# CV_converter_v06.net
KiCad netlist of a schematic drawn in EAGLE
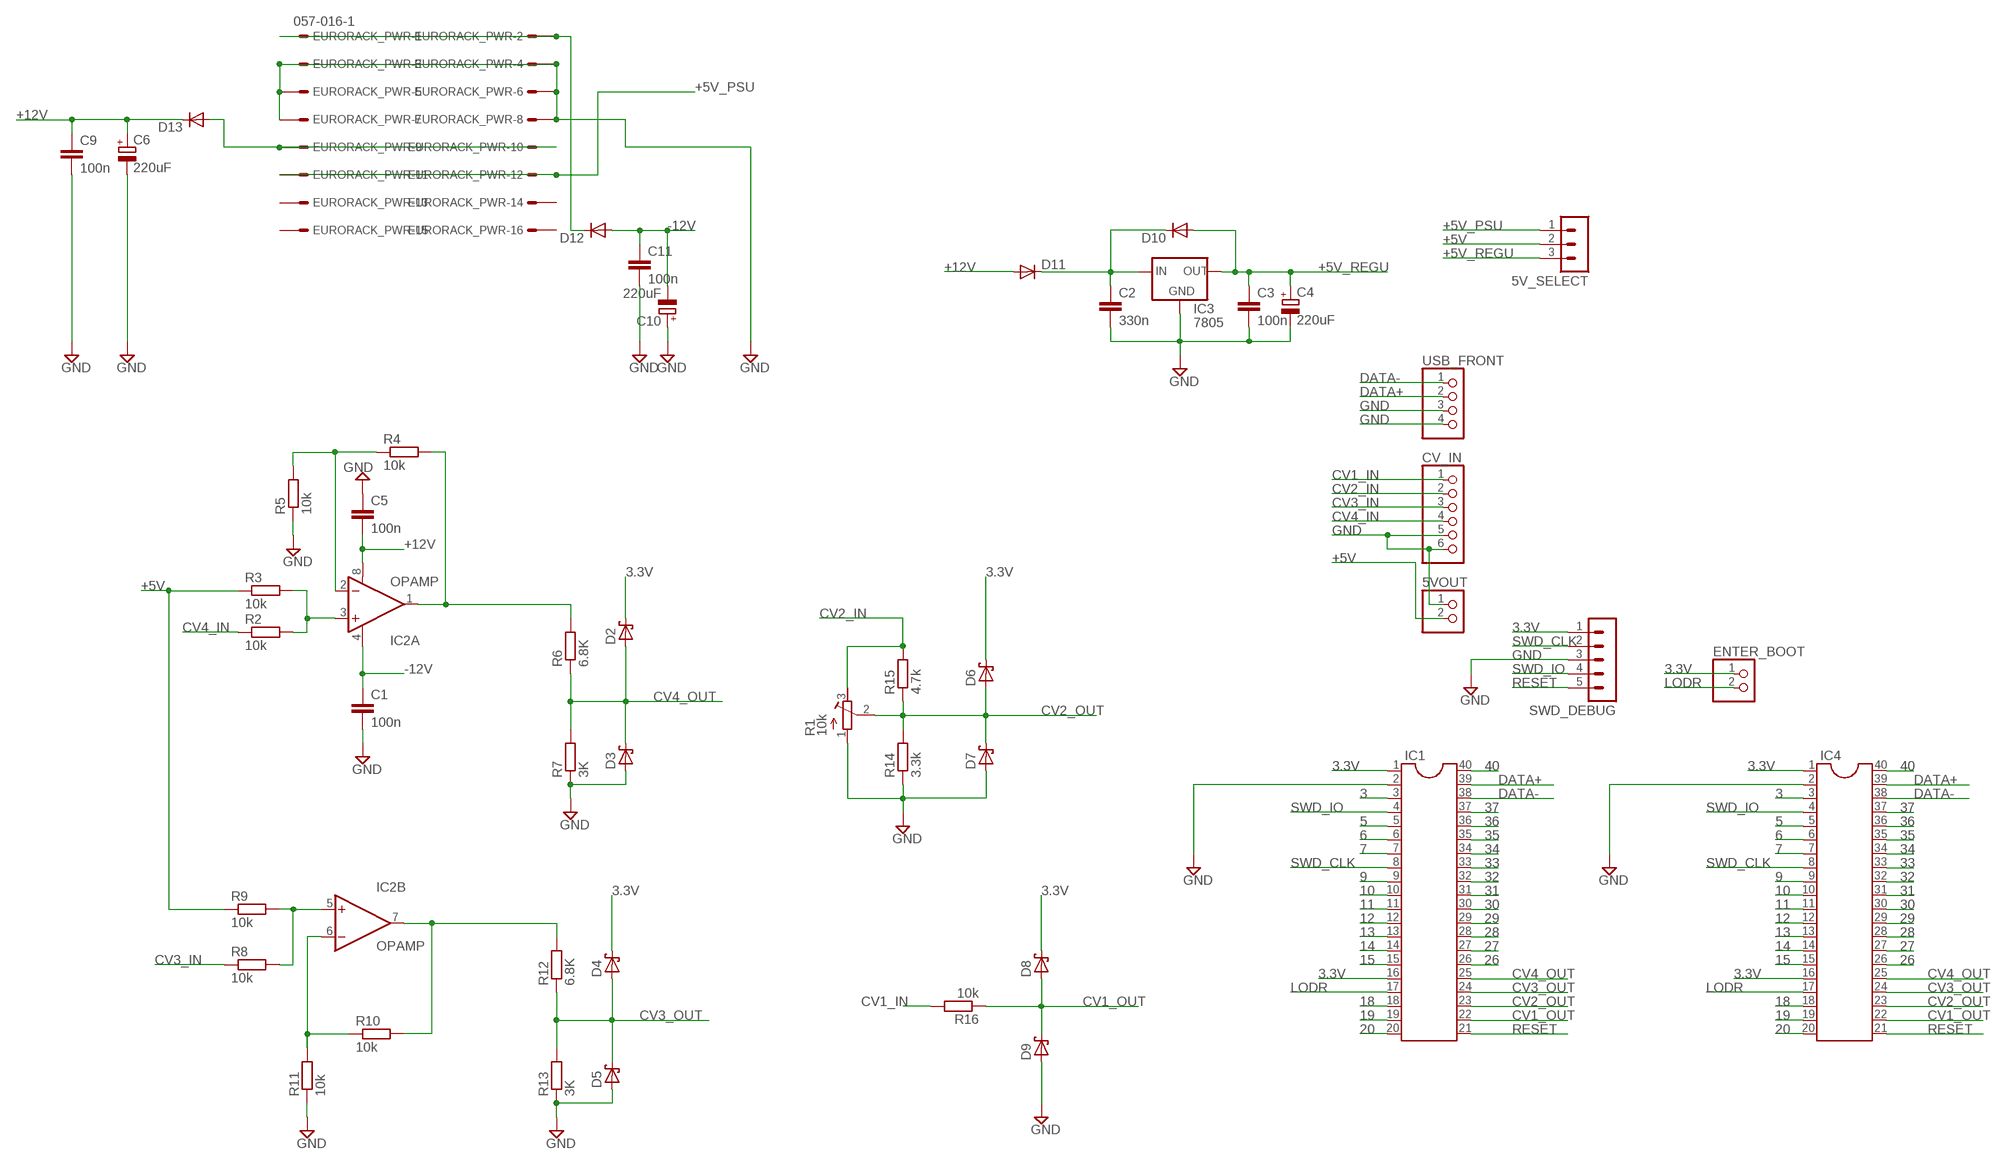
[diagram p0: schematic, sheet 1]

(export (version "E")
  (design (tool "Eeschema 10.0.6"))
  (components
    (comp (ref "5VOUT")
      (value "PINHD-1X2")
      (footprint "eagle-import:1X02")
      (libsource (lib "eagle-import") (part "pinhead_325_PINHD-1X2"))
    )
    (comp (ref "5V_SELECT")
      (value "MA03-1")
      (footprint "eagle-import:MA03-1")
      (libsource (lib "eagle-import") (part "MA03-1"))
    )
    (comp (ref "C1")
      (value "100n")
      (footprint "eagle-import:C025-025X050")
      (libsource (lib "eagle-import") (part "C-EU025-025X050"))
    )
    (comp (ref "C2")
      (value "330n")
      (footprint "eagle-import:C025-025X050")
      (libsource (lib "eagle-import") (part "C-EU025-025X050"))
    )
    (comp (ref "C3")
      (value "100n")
      (footprint "eagle-import:C025-025X050")
      (libsource (lib "eagle-import") (part "C-EU025-025X050"))
    )
    (comp (ref "C4")
      (value "220uF")
      (footprint "eagle-import:E2,5-7")
      (libsource (lib "eagle-import") (part "CPOL-EUE2.5-7"))
    )
    (comp (ref "C5")
      (value "100n")
      (footprint "eagle-import:C025-025X050")
      (libsource (lib "eagle-import") (part "C-EU025-025X050"))
    )
    (comp (ref "C6")
      (value "220uF")
      (footprint "eagle-import:E2,5-7")
      (libsource (lib "eagle-import") (part "CPOL-EUE2.5-7"))
    )
    (comp (ref "C9")
      (value "100n")
      (footprint "eagle-import:C025-025X050")
      (libsource (lib "eagle-import") (part "C-EU025-025X050"))
    )
    (comp (ref "C10")
      (value "220uF")
      (footprint "eagle-import:E2,5-7")
      (libsource (lib "eagle-import") (part "CPOL-EUE2.5-7"))
    )
    (comp (ref "C11")
      (value "100n")
      (footprint "eagle-import:C025-025X050")
      (libsource (lib "eagle-import") (part "C-EU025-025X050"))
    )
    (comp (ref "CV_IN")
      (value "PINHD-1X6")
      (footprint "eagle-import:1X06")
      (libsource (lib "eagle-import") (part "PINHD-1X6"))
    )
    (comp (ref "D2")
      (value "SCHOTTKY-DIODEDO35-7")
      (footprint "eagle-import:DO35-7")
      (libsource (lib "eagle-import") (part "SCHOTTKY-DIODEDO35-7"))
    )
    (comp (ref "D3")
      (value "SCHOTTKY-DIODEDO35-7")
      (footprint "eagle-import:DO35-7")
      (libsource (lib "eagle-import") (part "SCHOTTKY-DIODEDO35-7"))
    )
    (comp (ref "D4")
      (value "SCHOTTKY-DIODEDO35-7")
      (footprint "eagle-import:DO35-7")
      (libsource (lib "eagle-import") (part "SCHOTTKY-DIODEDO35-7"))
    )
    (comp (ref "D5")
      (value "SCHOTTKY-DIODEDO35-7")
      (footprint "eagle-import:DO35-7")
      (libsource (lib "eagle-import") (part "SCHOTTKY-DIODEDO35-7"))
    )
    (comp (ref "D6")
      (value "SCHOTTKY-DIODEDO35-7")
      (footprint "eagle-import:DO35-7")
      (libsource (lib "eagle-import") (part "SCHOTTKY-DIODEDO35-7"))
    )
    (comp (ref "D7")
      (value "SCHOTTKY-DIODEDO35-7")
      (footprint "eagle-import:DO35-7")
      (libsource (lib "eagle-import") (part "SCHOTTKY-DIODEDO35-7"))
    )
    (comp (ref "D8")
      (value "SCHOTTKY-DIODEDO35-7")
      (footprint "eagle-import:DO35-7")
      (libsource (lib "eagle-import") (part "SCHOTTKY-DIODEDO35-7"))
    )
    (comp (ref "D9")
      (value "SCHOTTKY-DIODEDO35-7")
      (footprint "eagle-import:DO35-7")
      (libsource (lib "eagle-import") (part "SCHOTTKY-DIODEDO35-7"))
    )
    (comp (ref "D10")
      (value "DIODE-D-7.5")
      (footprint "eagle-import:D-7.5")
      (libsource (lib "eagle-import") (part "DIODE-D-7.5"))
    )
    (comp (ref "D11")
      (value "DIODE-D-7.5")
      (footprint "eagle-import:D-7.5")
      (libsource (lib "eagle-import") (part "DIODE-D-7.5"))
    )
    (comp (ref "D12")
      (value "DIODE-D-7.5")
      (footprint "eagle-import:D-7.5")
      (libsource (lib "eagle-import") (part "DIODE-D-7.5"))
    )
    (comp (ref "D13")
      (value "DIODE-D-7.5")
      (footprint "eagle-import:D-7.5")
      (libsource (lib "eagle-import") (part "DIODE-D-7.5"))
    )
    (comp (ref "ENTER_BOOT")
      (value "PINHD-1X2")
      (footprint "eagle-import:1X02")
      (libsource (lib "eagle-import") (part "PINHD-1X2"))
    )
    (comp (ref "EURORACK_PWR")
      (value "057-016-1")
      (footprint "eagle-import:057-016-1")
      (libsource (lib "eagle-import") (part "057-016-1"))
    )
    (comp (ref "IC1")
      (value "DIL40")
      (footprint "eagle-import:DIL40")
      (libsource (lib "eagle-import") (part "DIL40"))
    )
    (comp (ref "IC2")
      (value "OPAMP")
      (footprint "eagle-import:DIP08")
      (libsource (lib "eagle-import") (part "OPAMP-DUALDIP"))
    )
    (comp (ref "IC3")
      (value "7805")
      (footprint "eagle-import:TO-220-ALT")
      (libsource (lib "eagle-import") (part "V_REG_78XX-TO-220"))
    )
    (comp (ref "IC4")
      (value "DIL40")
      (footprint "eagle-import:DIL40")
      (libsource (lib "eagle-import") (part "DIL40"))
    )
    (comp (ref "R1")
      (value "10k")
      (footprint "eagle-import:RTRIM64W")
      (libsource (lib "eagle-import") (part "R-TRIMM64W"))
    )
    (comp (ref "R2")
      (value "10k")
      (footprint "eagle-import:0207_7")
      (libsource (lib "eagle-import") (part "R-EU_0207/7"))
    )
    (comp (ref "R3")
      (value "10k")
      (footprint "eagle-import:0207_7")
      (libsource (lib "eagle-import") (part "R-EU_0207/7"))
    )
    (comp (ref "R4")
      (value "10k")
      (footprint "eagle-import:0207_7")
      (libsource (lib "eagle-import") (part "R-EU_0207/7"))
    )
    (comp (ref "R5")
      (value "10k")
      (footprint "eagle-import:0207_7")
      (libsource (lib "eagle-import") (part "R-EU_0207/7"))
    )
    (comp (ref "R6")
      (value "6.8K")
      (footprint "eagle-import:0207_7")
      (libsource (lib "eagle-import") (part "R-EU_0207/7"))
    )
    (comp (ref "R7")
      (value "3K")
      (footprint "eagle-import:0207_7")
      (libsource (lib "eagle-import") (part "R-EU_0207/7"))
    )
    (comp (ref "R8")
      (value "10k")
      (footprint "eagle-import:0207_7")
      (libsource (lib "eagle-import") (part "R-EU_0207/7"))
    )
    (comp (ref "R9")
      (value "10k")
      (footprint "eagle-import:0207_7")
      (libsource (lib "eagle-import") (part "R-EU_0207/7"))
    )
    (comp (ref "R10")
      (value "10k")
      (footprint "eagle-import:0207_7")
      (libsource (lib "eagle-import") (part "R-EU_0207/7"))
    )
    (comp (ref "R11")
      (value "10k")
      (footprint "eagle-import:0207_7")
      (libsource (lib "eagle-import") (part "R-EU_0207/7"))
    )
    (comp (ref "R12")
      (value "6.8K")
      (footprint "eagle-import:0207_7")
      (libsource (lib "eagle-import") (part "R-EU_0207/7"))
    )
    (comp (ref "R13")
      (value "3K")
      (footprint "eagle-import:0207_7")
      (libsource (lib "eagle-import") (part "R-EU_0207/7"))
    )
    (comp (ref "R14")
      (value "3.3k")
      (footprint "eagle-import:0207_7")
      (libsource (lib "eagle-import") (part "R-EU_0207/7"))
    )
    (comp (ref "R15")
      (value "4.7k")
      (footprint "eagle-import:0207_7")
      (libsource (lib "eagle-import") (part "R-EU_0207/7"))
    )
    (comp (ref "R16")
      (value "10k")
      (footprint "eagle-import:0207_7")
      (libsource (lib "eagle-import") (part "R-EU_0207/7"))
    )
    (comp (ref "SWD_DEBUG")
      (value "MA05-1")
      (footprint "eagle-import:MA05-1")
      (libsource (lib "eagle-import") (part "MA05-1"))
    )
    (comp (ref "USB_FRONT")
      (value "PINHD-1X4")
      (footprint "eagle-import:1X04")
      (libsource (lib "eagle-import") (part "PINHD-1X4"))
    )
  )
  (nets
    (net (code "1") (name "/+5V") (class "Default")
      (node (ref "5VOUT") (pin "2") (pinfunction "2_2") (pintype "passive"))
      (node (ref "5V_SELECT") (pin "2") (pinfunction "2_2") (pintype "passive"))
      (node (ref "R3") (pin "1") (pinfunction "1_1") (pintype "passive"))
      (node (ref "R9") (pin "1") (pinfunction "1_1") (pintype "passive"))
    )
    (net (code "2") (name "/+5V_PSU") (class "Default")
      (node (ref "5V_SELECT") (pin "1") (pinfunction "1_1") (pintype "passive"))
      (node (ref "EURORACK_PWR") (pin "11") (pinfunction "S_11") (pintype "passive"))
      (node (ref "EURORACK_PWR") (pin "12") (pinfunction "S_12") (pintype "passive"))
    )
    (net (code "3") (name "/+5V_REGU") (class "Default")
      (node (ref "5V_SELECT") (pin "3") (pinfunction "3_3") (pintype "passive"))
      (node (ref "C3") (pin "1") (pinfunction "1_1") (pintype "passive"))
      (node (ref "C4") (pin "+") (pinfunction "+_+") (pintype "passive"))
      (node (ref "D10") (pin "A") (pinfunction "A_A") (pintype "passive"))
      (node (ref "IC3") (pin "OUT") (pinfunction "OUT_OUT") (pintype "output"))
    )
    (net (code "4") (name "/+12V") (class "Default")
      (node (ref "C5") (pin "2") (pinfunction "2_2") (pintype "passive"))
      (node (ref "C6") (pin "+") (pinfunction "+_+") (pintype "passive"))
      (node (ref "C9") (pin "1") (pinfunction "1_1") (pintype "passive"))
      (node (ref "D11") (pin "A") (pinfunction "A_A") (pintype "passive"))
      (node (ref "D13") (pin "C") (pinfunction "C_C") (pintype "passive"))
      (node (ref "IC2") (pin "8") (pinfunction "V+_8") (pintype "power_in"))
    )
    (net (code "5") (name "/-12V") (class "Default")
      (node (ref "C1") (pin "1") (pinfunction "1_1") (pintype "passive"))
      (node (ref "C10") (pin "-") (pinfunction "-_-") (pintype "passive"))
      (node (ref "C11") (pin "1") (pinfunction "1_1") (pintype "passive"))
      (node (ref "D12") (pin "A") (pinfunction "A_A") (pintype "passive"))
      (node (ref "IC2") (pin "4") (pinfunction "V-_4") (pintype "power_in"))
    )
    (net (code "6") (name "/3") (class "Default")
      (node (ref "IC1") (pin "3") (pinfunction "3_3") (pintype "passive"))
      (node (ref "IC4") (pin "3") (pinfunction "3_3") (pintype "passive"))
    )
    (net (code "7") (name "/3.3V") (class "Default")
      (node (ref "D2") (pin "C") (pinfunction "C_C") (pintype "passive"))
      (node (ref "D4") (pin "C") (pinfunction "C_C") (pintype "passive"))
      (node (ref "D6") (pin "C") (pinfunction "C_C") (pintype "passive"))
      (node (ref "D8") (pin "C") (pinfunction "C_C") (pintype "passive"))
      (node (ref "ENTER_BOOT") (pin "1") (pinfunction "1_1") (pintype "passive"))
      (node (ref "IC1") (pin "1") (pinfunction "1_1") (pintype "passive"))
      (node (ref "IC1") (pin "16") (pinfunction "16_16") (pintype "passive"))
      (node (ref "IC4") (pin "1") (pinfunction "1_1") (pintype "passive"))
      (node (ref "IC4") (pin "16") (pinfunction "16_16") (pintype "passive"))
      (node (ref "SWD_DEBUG") (pin "1") (pinfunction "1_1") (pintype "passive"))
    )
    (net (code "8") (name "/5") (class "Default")
      (node (ref "IC1") (pin "5") (pinfunction "5_5") (pintype "passive"))
      (node (ref "IC4") (pin "5") (pinfunction "5_5") (pintype "passive"))
    )
    (net (code "9") (name "/6") (class "Default")
      (node (ref "IC1") (pin "6") (pinfunction "6_6") (pintype "passive"))
      (node (ref "IC4") (pin "6") (pinfunction "6_6") (pintype "passive"))
    )
    (net (code "10") (name "/7") (class "Default")
      (node (ref "IC1") (pin "7") (pinfunction "7_7") (pintype "passive"))
      (node (ref "IC4") (pin "7") (pinfunction "7_7") (pintype "passive"))
    )
    (net (code "11") (name "/9") (class "Default")
      (node (ref "IC1") (pin "9") (pinfunction "9_9") (pintype "passive"))
      (node (ref "IC4") (pin "9") (pinfunction "9_9") (pintype "passive"))
    )
    (net (code "12") (name "/10") (class "Default")
      (node (ref "IC1") (pin "10") (pinfunction "10_10") (pintype "passive"))
      (node (ref "IC4") (pin "10") (pinfunction "10_10") (pintype "passive"))
    )
    (net (code "13") (name "/11") (class "Default")
      (node (ref "IC1") (pin "11") (pinfunction "11_11") (pintype "passive"))
      (node (ref "IC4") (pin "11") (pinfunction "11_11") (pintype "passive"))
    )
    (net (code "14") (name "/12") (class "Default")
      (node (ref "IC1") (pin "12") (pinfunction "12_12") (pintype "passive"))
      (node (ref "IC4") (pin "12") (pinfunction "12_12") (pintype "passive"))
    )
    (net (code "15") (name "/13") (class "Default")
      (node (ref "IC1") (pin "13") (pinfunction "13_13") (pintype "passive"))
      (node (ref "IC4") (pin "13") (pinfunction "13_13") (pintype "passive"))
    )
    (net (code "16") (name "/14") (class "Default")
      (node (ref "IC1") (pin "14") (pinfunction "14_14") (pintype "passive"))
      (node (ref "IC4") (pin "14") (pinfunction "14_14") (pintype "passive"))
    )
    (net (code "17") (name "/15") (class "Default")
      (node (ref "IC1") (pin "15") (pinfunction "15_15") (pintype "passive"))
      (node (ref "IC4") (pin "15") (pinfunction "15_15") (pintype "passive"))
    )
    (net (code "18") (name "/18") (class "Default")
      (node (ref "IC1") (pin "18") (pinfunction "18_18") (pintype "passive"))
      (node (ref "IC4") (pin "18") (pinfunction "18_18") (pintype "passive"))
    )
    (net (code "19") (name "/19") (class "Default")
      (node (ref "IC1") (pin "19") (pinfunction "19_19") (pintype "passive"))
      (node (ref "IC4") (pin "19") (pinfunction "19_19") (pintype "passive"))
    )
    (net (code "20") (name "/20") (class "Default")
      (node (ref "IC1") (pin "20") (pinfunction "20_20") (pintype "passive"))
      (node (ref "IC4") (pin "20") (pinfunction "20_20") (pintype "passive"))
    )
    (net (code "21") (name "/26") (class "Default")
      (node (ref "IC1") (pin "26") (pinfunction "26_26") (pintype "passive"))
      (node (ref "IC4") (pin "26") (pinfunction "26_26") (pintype "passive"))
    )
    (net (code "22") (name "/27") (class "Default")
      (node (ref "IC1") (pin "27") (pinfunction "27_27") (pintype "passive"))
      (node (ref "IC4") (pin "27") (pinfunction "27_27") (pintype "passive"))
    )
    (net (code "23") (name "/28") (class "Default")
      (node (ref "IC1") (pin "28") (pinfunction "28_28") (pintype "passive"))
      (node (ref "IC4") (pin "28") (pinfunction "28_28") (pintype "passive"))
    )
    (net (code "24") (name "/29") (class "Default")
      (node (ref "IC1") (pin "29") (pinfunction "29_29") (pintype "passive"))
      (node (ref "IC4") (pin "29") (pinfunction "29_29") (pintype "passive"))
    )
    (net (code "25") (name "/30") (class "Default")
      (node (ref "IC1") (pin "30") (pinfunction "30_30") (pintype "passive"))
      (node (ref "IC4") (pin "30") (pinfunction "30_30") (pintype "passive"))
    )
    (net (code "26") (name "/31") (class "Default")
      (node (ref "IC1") (pin "31") (pinfunction "31_31") (pintype "passive"))
      (node (ref "IC4") (pin "31") (pinfunction "31_31") (pintype "passive"))
    )
    (net (code "27") (name "/32") (class "Default")
      (node (ref "IC1") (pin "32") (pinfunction "32_32") (pintype "passive"))
      (node (ref "IC4") (pin "32") (pinfunction "32_32") (pintype "passive"))
    )
    (net (code "28") (name "/33") (class "Default")
      (node (ref "IC1") (pin "33") (pinfunction "33_33") (pintype "passive"))
      (node (ref "IC4") (pin "33") (pinfunction "33_33") (pintype "passive"))
    )
    (net (code "29") (name "/34") (class "Default")
      (node (ref "IC1") (pin "34") (pinfunction "34_34") (pintype "passive"))
      (node (ref "IC4") (pin "34") (pinfunction "34_34") (pintype "passive"))
    )
    (net (code "30") (name "/35") (class "Default")
      (node (ref "IC1") (pin "35") (pinfunction "35_35") (pintype "passive"))
      (node (ref "IC4") (pin "35") (pinfunction "35_35") (pintype "passive"))
    )
    (net (code "31") (name "/36") (class "Default")
      (node (ref "IC1") (pin "36") (pinfunction "36_36") (pintype "passive"))
      (node (ref "IC4") (pin "36") (pinfunction "36_36") (pintype "passive"))
    )
    (net (code "32") (name "/37") (class "Default")
      (node (ref "IC1") (pin "37") (pinfunction "37_37") (pintype "passive"))
      (node (ref "IC4") (pin "37") (pinfunction "37_37") (pintype "passive"))
    )
    (net (code "33") (name "/40") (class "Default")
      (node (ref "IC1") (pin "40") (pinfunction "40_40") (pintype "passive"))
      (node (ref "IC4") (pin "40") (pinfunction "40_40") (pintype "passive"))
    )
    (net (code "34") (name "/CV1_IN") (class "Default")
      (node (ref "CV_IN") (pin "1") (pinfunction "1_1") (pintype "passive"))
      (node (ref "R16") (pin "2") (pinfunction "2_2") (pintype "passive"))
    )
    (net (code "35") (name "/CV1_OUT") (class "Default")
      (node (ref "D8") (pin "A") (pinfunction "A_A") (pintype "passive"))
      (node (ref "D9") (pin "C") (pinfunction "C_C") (pintype "passive"))
      (node (ref "IC1") (pin "22") (pinfunction "22_22") (pintype "passive"))
      (node (ref "IC4") (pin "22") (pinfunction "22_22") (pintype "passive"))
      (node (ref "R16") (pin "1") (pinfunction "1_1") (pintype "passive"))
    )
    (net (code "36") (name "/CV2_IN") (class "Default")
      (node (ref "CV_IN") (pin "2") (pinfunction "2_2") (pintype "passive"))
      (node (ref "R1") (pin "3") (pinfunction "E_3") (pintype "passive"))
      (node (ref "R15") (pin "2") (pinfunction "2_2") (pintype "passive"))
    )
    (net (code "37") (name "/CV2_OUT") (class "Default")
      (node (ref "D6") (pin "A") (pinfunction "A_A") (pintype "passive"))
      (node (ref "D7") (pin "C") (pinfunction "C_C") (pintype "passive"))
      (node (ref "IC1") (pin "23") (pinfunction "23_23") (pintype "passive"))
      (node (ref "IC4") (pin "23") (pinfunction "23_23") (pintype "passive"))
      (node (ref "R1") (pin "2") (pinfunction "S_2") (pintype "passive"))
      (node (ref "R14") (pin "2") (pinfunction "2_2") (pintype "passive"))
      (node (ref "R15") (pin "1") (pinfunction "1_1") (pintype "passive"))
    )
    (net (code "38") (name "/CV3_IN") (class "Default")
      (node (ref "CV_IN") (pin "3") (pinfunction "3_3") (pintype "passive"))
      (node (ref "R8") (pin "1") (pinfunction "1_1") (pintype "passive"))
    )
    (net (code "39") (name "/CV3_OUT") (class "Default")
      (node (ref "D4") (pin "A") (pinfunction "A_A") (pintype "passive"))
      (node (ref "D5") (pin "C") (pinfunction "C_C") (pintype "passive"))
      (node (ref "IC1") (pin "24") (pinfunction "24_24") (pintype "passive"))
      (node (ref "IC4") (pin "24") (pinfunction "24_24") (pintype "passive"))
      (node (ref "R12") (pin "1") (pinfunction "1_1") (pintype "passive"))
      (node (ref "R13") (pin "2") (pinfunction "2_2") (pintype "passive"))
    )
    (net (code "40") (name "/CV4_IN") (class "Default")
      (node (ref "CV_IN") (pin "4") (pinfunction "4_4") (pintype "passive"))
      (node (ref "R2") (pin "1") (pinfunction "1_1") (pintype "passive"))
    )
    (net (code "41") (name "/CV4_OUT") (class "Default")
      (node (ref "D2") (pin "A") (pinfunction "A_A") (pintype "passive"))
      (node (ref "D3") (pin "C") (pinfunction "C_C") (pintype "passive"))
      (node (ref "IC1") (pin "25") (pinfunction "25_25") (pintype "passive"))
      (node (ref "IC4") (pin "25") (pinfunction "25_25") (pintype "passive"))
      (node (ref "R6") (pin "1") (pinfunction "1_1") (pintype "passive"))
      (node (ref "R7") (pin "2") (pinfunction "2_2") (pintype "passive"))
    )
    (net (code "42") (name "/DATA+") (class "Default")
      (node (ref "IC1") (pin "39") (pinfunction "39_39") (pintype "passive"))
      (node (ref "IC4") (pin "39") (pinfunction "39_39") (pintype "passive"))
      (node (ref "USB_FRONT") (pin "2") (pinfunction "2_2") (pintype "passive"))
    )
    (net (code "43") (name "/DATA-") (class "Default")
      (node (ref "IC1") (pin "38") (pinfunction "38_38") (pintype "passive"))
      (node (ref "IC4") (pin "38") (pinfunction "38_38") (pintype "passive"))
      (node (ref "USB_FRONT") (pin "1") (pinfunction "1_1") (pintype "passive"))
    )
    (net (code "44") (name "/LODR") (class "Default")
      (node (ref "ENTER_BOOT") (pin "2") (pinfunction "2_2") (pintype "passive"))
      (node (ref "IC1") (pin "17") (pinfunction "17_17") (pintype "passive"))
      (node (ref "IC4") (pin "17") (pinfunction "17_17") (pintype "passive"))
    )
    (net (code "45") (name "/RESET") (class "Default")
      (node (ref "IC1") (pin "21") (pinfunction "21_21") (pintype "passive"))
      (node (ref "IC4") (pin "21") (pinfunction "21_21") (pintype "passive"))
      (node (ref "SWD_DEBUG") (pin "5") (pinfunction "5_5") (pintype "passive"))
    )
    (net (code "46") (name "/SWD_CLK") (class "Default")
      (node (ref "IC1") (pin "8") (pinfunction "8_8") (pintype "passive"))
      (node (ref "IC4") (pin "8") (pinfunction "8_8") (pintype "passive"))
      (node (ref "SWD_DEBUG") (pin "2") (pinfunction "2_2") (pintype "passive"))
    )
    (net (code "47") (name "/SWD_IO") (class "Default")
      (node (ref "IC1") (pin "4") (pinfunction "4_4") (pintype "passive"))
      (node (ref "IC4") (pin "4") (pinfunction "4_4") (pintype "passive"))
      (node (ref "SWD_DEBUG") (pin "4") (pinfunction "4_4") (pintype "passive"))
    )
    (net (code "48") (name "GND") (class "Default")
      (node (ref "5VOUT") (pin "1") (pinfunction "1_1") (pintype "passive"))
      (node (ref "C1") (pin "2") (pinfunction "2_2") (pintype "passive"))
      (node (ref "C10") (pin "+") (pinfunction "+_+") (pintype "passive"))
      (node (ref "C11") (pin "2") (pinfunction "2_2") (pintype "passive"))
      (node (ref "C2") (pin "2") (pinfunction "2_2") (pintype "passive"))
      (node (ref "C3") (pin "2") (pinfunction "2_2") (pintype "passive"))
      (node (ref "C4") (pin "-") (pinfunction "-_-") (pintype "passive"))
      (node (ref "C5") (pin "1") (pinfunction "1_1") (pintype "passive"))
      (node (ref "C6") (pin "-") (pinfunction "-_-") (pintype "passive"))
      (node (ref "C9") (pin "2") (pinfunction "2_2") (pintype "passive"))
      (node (ref "CV_IN") (pin "5") (pinfunction "5_5") (pintype "passive"))
      (node (ref "CV_IN") (pin "6") (pinfunction "6_6") (pintype "passive"))
      (node (ref "D3") (pin "A") (pinfunction "A_A") (pintype "passive"))
      (node (ref "D5") (pin "A") (pinfunction "A_A") (pintype "passive"))
      (node (ref "D7") (pin "A") (pinfunction "A_A") (pintype "passive"))
      (node (ref "D9") (pin "A") (pinfunction "A_A") (pintype "passive"))
      (node (ref "EURORACK_PWR") (pin "3") (pinfunction "S_3") (pintype "passive"))
      (node (ref "EURORACK_PWR") (pin "4") (pinfunction "S_4") (pintype "passive"))
      (node (ref "EURORACK_PWR") (pin "5") (pinfunction "S_5") (pintype "passive"))
      (node (ref "EURORACK_PWR") (pin "6") (pinfunction "S_6") (pintype "passive"))
      (node (ref "EURORACK_PWR") (pin "7") (pinfunction "S_7") (pintype "passive"))
      (node (ref "EURORACK_PWR") (pin "8") (pinfunction "S_8") (pintype "passive"))
      (node (ref "IC1") (pin "2") (pinfunction "2_2") (pintype "passive"))
      (node (ref "IC3") (pin "GND") (pinfunction "GND_GND") (pintype "input"))
      (node (ref "IC4") (pin "2") (pinfunction "2_2") (pintype "passive"))
      (node (ref "R1") (pin "1") (pinfunction "A_1") (pintype "passive"))
      (node (ref "R11") (pin "1") (pinfunction "1_1") (pintype "passive"))
      (node (ref "R13") (pin "1") (pinfunction "1_1") (pintype "passive"))
      (node (ref "R14") (pin "1") (pinfunction "1_1") (pintype "passive"))
      (node (ref "R5") (pin "1") (pinfunction "1_1") (pintype "passive"))
      (node (ref "R7") (pin "1") (pinfunction "1_1") (pintype "passive"))
      (node (ref "SWD_DEBUG") (pin "3") (pinfunction "3_3") (pintype "passive"))
      (node (ref "USB_FRONT") (pin "3") (pinfunction "3_3") (pintype "passive"))
      (node (ref "USB_FRONT") (pin "4") (pinfunction "4_4") (pintype "passive"))
    )
    (net (code "49") (name "Net-(C2-Pad1)") (class "Default")
      (node (ref "C2") (pin "1") (pinfunction "1_1") (pintype "passive"))
      (node (ref "D10") (pin "C") (pinfunction "C_C") (pintype "passive"))
      (node (ref "D11") (pin "C") (pinfunction "C_C") (pintype "passive"))
      (node (ref "IC3") (pin "IN") (pinfunction "IN_IN") (pintype "input"))
    )
    (net (code "50") (name "Net-(EURORACK_PWRA-S)") (class "Default")
      (node (ref "D12") (pin "C") (pinfunction "C_C") (pintype "passive"))
      (node (ref "EURORACK_PWR") (pin "1") (pinfunction "S_1") (pintype "passive"))
      (node (ref "EURORACK_PWR") (pin "2") (pinfunction "S_2") (pintype "passive"))
    )
    (net (code "51") (name "Net-(EURORACK_PWRB-S)") (class "Default")
      (node (ref "D13") (pin "A") (pinfunction "A_A") (pintype "passive"))
      (node (ref "EURORACK_PWR") (pin "10") (pinfunction "S_10") (pintype "passive"))
      (node (ref "EURORACK_PWR") (pin "9") (pinfunction "S_9") (pintype "passive"))
    )
    (net (code "52") (name "Net-(IC2A-+IN)") (class "Default")
      (node (ref "IC2") (pin "3") (pinfunction "+IN_3") (pintype "input"))
      (node (ref "R2") (pin "2") (pinfunction "2_2") (pintype "passive"))
      (node (ref "R3") (pin "2") (pinfunction "2_2") (pintype "passive"))
    )
    (net (code "53") (name "Net-(IC2A--IN)") (class "Default")
      (node (ref "IC2") (pin "2") (pinfunction "-IN_2") (pintype "input"))
      (node (ref "R4") (pin "1") (pinfunction "1_1") (pintype "passive"))
      (node (ref "R5") (pin "2") (pinfunction "2_2") (pintype "passive"))
    )
    (net (code "54") (name "Net-(IC2A-OUT)") (class "Default")
      (node (ref "IC2") (pin "1") (pinfunction "OUT_1") (pintype "output"))
      (node (ref "R4") (pin "2") (pinfunction "2_2") (pintype "passive"))
      (node (ref "R6") (pin "2") (pinfunction "2_2") (pintype "passive"))
    )
    (net (code "55") (name "Net-(IC2B-+IN)") (class "Default")
      (node (ref "IC2") (pin "5") (pinfunction "+IN_5") (pintype "input"))
      (node (ref "R8") (pin "2") (pinfunction "2_2") (pintype "passive"))
      (node (ref "R9") (pin "2") (pinfunction "2_2") (pintype "passive"))
    )
    (net (code "56") (name "Net-(IC2B--IN)") (class "Default")
      (node (ref "IC2") (pin "6") (pinfunction "-IN_6") (pintype "input"))
      (node (ref "R10") (pin "1") (pinfunction "1_1") (pintype "passive"))
      (node (ref "R11") (pin "2") (pinfunction "2_2") (pintype "passive"))
    )
    (net (code "57") (name "Net-(IC2B-OUT)") (class "Default")
      (node (ref "IC2") (pin "7") (pinfunction "OUT_7") (pintype "output"))
      (node (ref "R10") (pin "2") (pinfunction "2_2") (pintype "passive"))
      (node (ref "R12") (pin "2") (pinfunction "2_2") (pintype "passive"))
    )
    (net (code "58") (name "unconnected-(EURORACK_PWRE-S-Pad13)") (class "Default")
      (node (ref "EURORACK_PWR") (pin "13") (pinfunction "S_13") (pintype "passive"))
    )
    (net (code "59") (name "unconnected-(EURORACK_PWRF-S-Pad14)") (class "Default")
      (node (ref "EURORACK_PWR") (pin "14") (pinfunction "S_14") (pintype "passive"))
    )
    (net (code "60") (name "unconnected-(EURORACK_PWRG-S-Pad15)") (class "Default")
      (node (ref "EURORACK_PWR") (pin "15") (pinfunction "S_15") (pintype "passive"))
    )
    (net (code "61") (name "unconnected-(EURORACK_PWRH-S-Pad16)") (class "Default")
      (node (ref "EURORACK_PWR") (pin "16") (pinfunction "S_16") (pintype "passive"))
    )
  )
)
